# AUDIO_CODEC_CS4270-B.net
KiCad netlist of a schematic drawn in Altium Designer
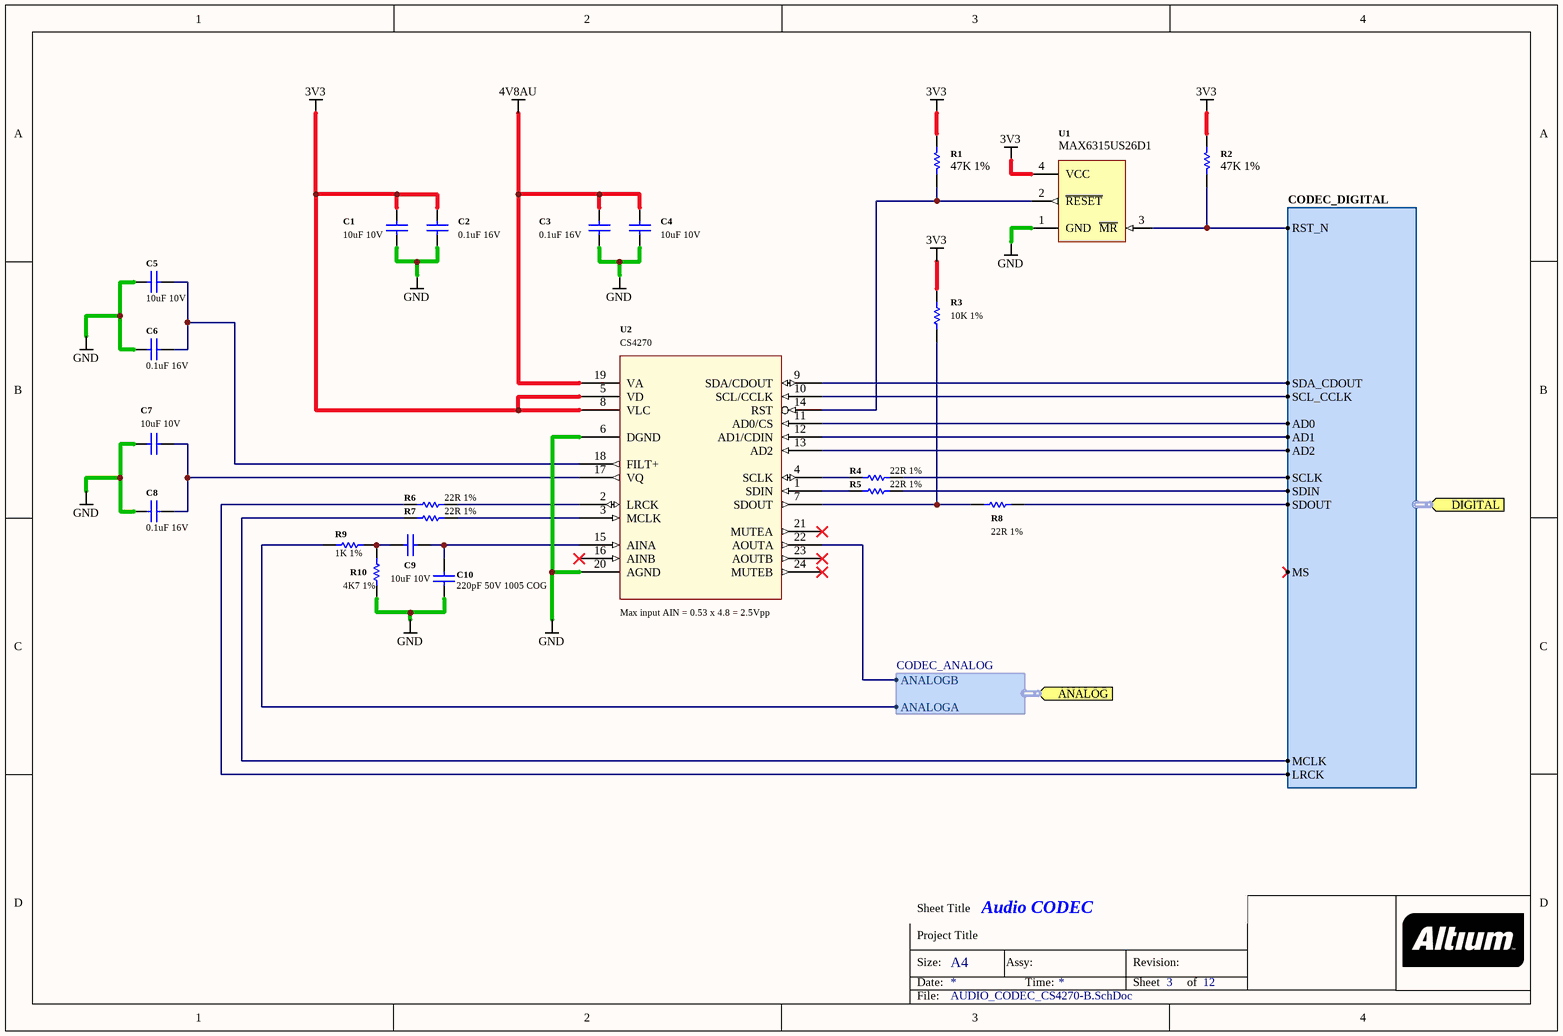
[diagram p0: AUDIO_CODEC_CS4270-B.SchDoc]

(export (version "E")
  (design (tool "Eeschema 10.0.6"))
  (components
    (comp (ref "C1")
      (value "10uF 10V")
      (footprint "CAPC2012-STAR")
      (description "Capacitor, Ceramic, 10uF 10% 10V 0805 (2012) X5R")
      (fields (field (name "TOLERANCE") "10 %"))
      (libsource (lib "AltiumDesignLibrary") (part "CAP-NP"))
    )
    (comp (ref "C2")
      (value "0.1uF 16V")
      (footprint "CAPC1005-STAR")
      (description "Capacitor, Ceramic, 0.1uF 10% 16V 0402 (1005) X7R")
      (fields (field (name "TOLERANCE") "10 %"))
      (libsource (lib "AltiumDesignLibrary") (part "CAP-NP"))
    )
    (comp (ref "C3")
      (value "0.1uF 16V")
      (footprint "CAPC1005-STAR")
      (description "Capacitor, Ceramic, 0.1uF 10% 16V 0402 (1005) X7R")
      (fields (field (name "TOLERANCE") "10 %"))
      (libsource (lib "AltiumDesignLibrary") (part "CAP-NP"))
    )
    (comp (ref "C4")
      (value "10uF 10V")
      (footprint "CAPC2012-STAR")
      (description "Capacitor, Ceramic, 10uF 10% 10V 0805 (2012) X5R")
      (fields (field (name "TOLERANCE") "10 %"))
      (libsource (lib "AltiumDesignLibrary") (part "CAP-NP"))
    )
    (comp (ref "C5")
      (value "10uF 10V")
      (footprint "CAPC2012-STAR")
      (description "Capacitor, Ceramic, 10uF 10% 10V 0805 (2012) X5R")
      (fields (field (name "TOLERANCE") "10 %"))
      (libsource (lib "AltiumDesignLibrary") (part "CAP-NP"))
    )
    (comp (ref "C6")
      (value "0.1uF 16V")
      (footprint "CAPC1005-STAR")
      (description "Capacitor, Ceramic, 0.1uF 10% 16V 0402 (1005) X7R")
      (fields (field (name "TOLERANCE") "10 %"))
      (libsource (lib "AltiumDesignLibrary") (part "CAP-NP"))
    )
    (comp (ref "C7")
      (value "10uF 10V")
      (footprint "CAPC2012-STAR")
      (description "Capacitor, Ceramic, 10uF 10% 10V 0805 (2012) X5R")
      (fields (field (name "TOLERANCE") "10 %"))
      (libsource (lib "AltiumDesignLibrary") (part "CAP-NP"))
    )
    (comp (ref "C8")
      (value "0.1uF 16V")
      (footprint "CAPC1005-STAR")
      (description "Capacitor, Ceramic, 0.1uF 10% 16V 0402 (1005) X7R")
      (fields (field (name "TOLERANCE") "10 %"))
      (libsource (lib "AltiumDesignLibrary") (part "CAP-NP"))
    )
    (comp (ref "C9")
      (value "10uF 10V")
      (footprint "CAPC2012-STAR")
      (description "Capacitor, Ceramic, 10uF 10% 10V 0805 (2012) X5R")
      (fields (field (name "TOLERANCE") "10 %"))
      (libsource (lib "AltiumDesignLibrary") (part "CAP-NP"))
    )
    (comp (ref "C10")
      (value "220pF 50V 1005 COG")
      (footprint "CAPC1005-STAR")
      (description "Capacitor, Ceramic, 220pF 5% 50V 0402 (1005) COG")
      (fields (field (name "TOLERANCE") "5 %"))
      (libsource (lib "AltiumDesignLibrary") (part "CAP-NP"))
    )
    (comp (ref "R1")
      (value "47K 1%")
      (footprint "RESC1005-STAR")
      (description "Resistor, 47K 1% 0402 (1005)")
      (fields (field (name "TOLERANCE") "1 %"))
      (libsource (lib "AltiumDesignLibrary") (part "RES"))
    )
    (comp (ref "R2")
      (value "47K 1%")
      (footprint "RESC1005-STAR")
      (description "Resistor, 47K 1% 0402 (1005)")
      (fields (field (name "TOLERANCE") "1 %"))
      (libsource (lib "AltiumDesignLibrary") (part "RES"))
    )
    (comp (ref "R3")
      (value "10K 1%")
      (footprint "RESC1005-STAR")
      (description "Resistor, 10K 1% 0402 (1005)")
      (fields (field (name "TOLERANCE") "1 %"))
      (libsource (lib "AltiumDesignLibrary") (part "RES"))
    )
    (comp (ref "R4")
      (value "22R 1%")
      (footprint "RESC1005-STAR")
      (description "Resistor, 22R 1% 0402 (1005)")
      (fields (field (name "TOLERANCE") "1 %"))
      (libsource (lib "AltiumDesignLibrary") (part "RES"))
    )
    (comp (ref "R5")
      (value "22R 1%")
      (footprint "RESC1005-STAR")
      (description "Resistor, 22R 1% 0402 (1005)")
      (fields (field (name "TOLERANCE") "1 %"))
      (libsource (lib "AltiumDesignLibrary") (part "RES"))
    )
    (comp (ref "R6")
      (value "22R 1%")
      (footprint "RESC1005-STAR")
      (description "Resistor, 22R 1% 0402 (1005)")
      (fields (field (name "TOLERANCE") "1 %"))
      (libsource (lib "AltiumDesignLibrary") (part "RES"))
    )
    (comp (ref "R7")
      (value "22R 1%")
      (footprint "RESC1005-STAR")
      (description "Resistor, 22R 1% 0402 (1005)")
      (fields (field (name "TOLERANCE") "1 %"))
      (libsource (lib "AltiumDesignLibrary") (part "RES"))
    )
    (comp (ref "R8")
      (value "22R 1%")
      (footprint "RESC1005-STAR")
      (description "Resistor, 22R 1% 0402 (1005)")
      (fields (field (name "TOLERANCE") "1 %"))
      (libsource (lib "AltiumDesignLibrary") (part "RES"))
    )
    (comp (ref "R9")
      (value "1K 1%")
      (footprint "RESC1005-STAR")
      (description "Resistor, 1K 1% 0402 (1005)")
      (fields (field (name "TOLERANCE") "1 %"))
      (libsource (lib "AltiumDesignLibrary") (part "RES"))
    )
    (comp (ref "R10")
      (value "4K7 1%")
      (footprint "RESC1005-STAR")
      (description "Resistor, 4K7 1% 0402 (1005)")
      (fields (field (name "TOLERANCE") "1 %"))
      (libsource (lib "AltiumDesignLibrary") (part "RES"))
    )
    (comp (ref "U1")
      (value "MAX6315US26D1")
      (footprint "SOT143")
      (description "MAX6315, Open-Drain Output SOT Reset IC, Customized Reset Thresholds, Timeout Delays")
      (libsource (lib "AltiumDesignLibrary") (part "MAX6315"))
    )
    (comp (ref "U2")
      (value "CS4270")
      (footprint "TSSOP-24")
      (description "CS4270; 24-Bit, 192 kHz Stereo Audio CODEC")
      (libsource (lib "AltiumDesignLibrary") (part "CS4270"))
    )
  )
  (nets
    (net (code "3") (name "/AD0") (class "Default")
      (node (ref "U2") (pin "11") (pinfunction "AD0/CS_11") (pintype "input"))
    )
    (net (code "4") (name "/AD1") (class "Default")
      (node (ref "U2") (pin "12") (pinfunction "AD1/CDIN_12") (pintype "input"))
    )
    (net (code "5") (name "/AD2") (class "Default")
      (node (ref "U2") (pin "13") (pinfunction "AD2_13") (pintype "input"))
    )
    (net (code "6") (name "/ANALOGA") (class "Default")
      (node (ref "R9") (pin "1") (pinfunction "1_1") (pintype "passive"))
    )
    (net (code "7") (name "/ANALOGB") (class "Default")
      (node (ref "U2") (pin "22") (pinfunction "AOUTA_22") (pintype "output"))
    )
    (net (code "8") (name "/LRCK") (class "Default")
      (node (ref "R6") (pin "1") (pinfunction "1_1") (pintype "passive"))
    )
    (net (code "9") (name "/MCLK") (class "Default")
      (node (ref "R7") (pin "1") (pinfunction "1_1") (pintype "passive"))
    )
    (net (code "10") (name "/RST_N") (class "Default")
      (node (ref "R2") (pin "1") (pinfunction "1_1") (pintype "passive"))
      (node (ref "U1") (pin "3") (pinfunction "~{MR}_3") (pintype "input"))
    )
    (net (code "11") (name "/SCLK") (class "Default")
      (node (ref "R4") (pin "2") (pinfunction "2_2") (pintype "passive"))
    )
    (net (code "12") (name "/SCL_CCLK") (class "Default")
      (node (ref "U2") (pin "10") (pinfunction "SCL/CCLK_10") (pintype "input"))
    )
    (net (code "13") (name "/SDA_CDOUT") (class "Default")
      (node (ref "U2") (pin "9") (pinfunction "SDA/CDOUT_9") (pintype "bidirectional"))
    )
    (net (code "14") (name "/SDIN") (class "Default")
      (node (ref "R5") (pin "2") (pinfunction "2_2") (pintype "passive"))
    )
    (net (code "15") (name "/SDOUT") (class "Default")
      (node (ref "R8") (pin "2") (pinfunction "2_2") (pintype "passive"))
    )
    (net (code "18") (name "3V3") (class "Default")
      (node (ref "C1") (pin "1") (pinfunction "1_1") (pintype "passive"))
      (node (ref "C2") (pin "1") (pinfunction "1_1") (pintype "passive"))
      (node (ref "R1") (pin "2") (pinfunction "2_2") (pintype "passive"))
      (node (ref "R2") (pin "2") (pinfunction "2_2") (pintype "passive"))
      (node (ref "R3") (pin "1") (pinfunction "1_1") (pintype "passive"))
      (node (ref "U1") (pin "4") (pinfunction "VCC_4") (pintype "power_in"))
      (node (ref "U2") (pin "5") (pinfunction "VD_5") (pintype "power_in"))
      (node (ref "U2") (pin "8") (pinfunction "VLC_8") (pintype "power_in"))
    )
    (net (code "19") (name "4V8AU") (class "Default")
      (node (ref "C3") (pin "1") (pinfunction "1_1") (pintype "passive"))
      (node (ref "C4") (pin "1") (pinfunction "1_1") (pintype "passive"))
      (node (ref "U2") (pin "19") (pinfunction "VA_19") (pintype "power_in"))
    )
    (net (code "20") (name "GND") (class "Default")
      (node (ref "C1") (pin "2") (pinfunction "2_2") (pintype "passive"))
      (node (ref "C10") (pin "2") (pinfunction "2_2") (pintype "passive"))
      (node (ref "C2") (pin "2") (pinfunction "2_2") (pintype "passive"))
      (node (ref "C3") (pin "2") (pinfunction "2_2") (pintype "passive"))
      (node (ref "C4") (pin "2") (pinfunction "2_2") (pintype "passive"))
      (node (ref "C5") (pin "2") (pinfunction "2_2") (pintype "passive"))
      (node (ref "C6") (pin "1") (pinfunction "1_1") (pintype "passive"))
      (node (ref "C7") (pin "2") (pinfunction "2_2") (pintype "passive"))
      (node (ref "C8") (pin "2") (pinfunction "2_2") (pintype "passive"))
      (node (ref "R10") (pin "1") (pinfunction "1_1") (pintype "passive"))
      (node (ref "U1") (pin "1") (pinfunction "GND_1") (pintype "power_in"))
      (node (ref "U2") (pin "20") (pinfunction "AGND_20") (pintype "power_in"))
      (node (ref "U2") (pin "6") (pinfunction "DGND_6") (pintype "power_in"))
    )
    (net (code "21") (name "Net-(C9-Pad2)") (class "Default")
      (node (ref "C9") (pin "2") (pinfunction "2_2") (pintype "passive"))
      (node (ref "R10") (pin "2") (pinfunction "2_2") (pintype "passive"))
      (node (ref "R9") (pin "2") (pinfunction "2_2") (pintype "passive"))
    )
    (net (code "22") (name "Net-(U1-~{RESET})") (class "Default")
      (node (ref "R1") (pin "1") (pinfunction "1_1") (pintype "passive"))
      (node (ref "U1") (pin "2") (pinfunction "~{RESET}_2") (pintype "output"))
      (node (ref "U2") (pin "14") (pinfunction "RST_14") (pintype "input"))
    )
    (net (code "23") (name "Net-(U2-AINA)") (class "Default")
      (node (ref "C10") (pin "1") (pinfunction "1_1") (pintype "passive"))
      (node (ref "C9") (pin "1") (pinfunction "1_1") (pintype "passive"))
      (node (ref "U2") (pin "15") (pinfunction "AINA_15") (pintype "input"))
    )
    (net (code "24") (name "Net-(U2-FILT+)") (class "Default")
      (node (ref "C5") (pin "1") (pinfunction "1_1") (pintype "passive"))
      (node (ref "C6") (pin "2") (pinfunction "2_2") (pintype "passive"))
      (node (ref "U2") (pin "18") (pinfunction "FILT+_18") (pintype "output"))
    )
    (net (code "25") (name "Net-(U2-LRCK)") (class "Default")
      (node (ref "R6") (pin "2") (pinfunction "2_2") (pintype "passive"))
      (node (ref "U2") (pin "2") (pinfunction "LRCK_2") (pintype "bidirectional"))
    )
    (net (code "26") (name "Net-(U2-MCLK)") (class "Default")
      (node (ref "R7") (pin "2") (pinfunction "2_2") (pintype "passive"))
      (node (ref "U2") (pin "3") (pinfunction "MCLK_3") (pintype "input"))
    )
    (net (code "27") (name "Net-(U2-SCLK)") (class "Default")
      (node (ref "R4") (pin "1") (pinfunction "1_1") (pintype "passive"))
      (node (ref "U2") (pin "4") (pinfunction "SCLK_4") (pintype "bidirectional"))
    )
    (net (code "28") (name "Net-(U2-SDIN)") (class "Default")
      (node (ref "R5") (pin "1") (pinfunction "1_1") (pintype "passive"))
      (node (ref "U2") (pin "1") (pinfunction "SDIN_1") (pintype "input"))
    )
    (net (code "29") (name "Net-(U2-SDOUT)") (class "Default")
      (node (ref "R3") (pin "2") (pinfunction "2_2") (pintype "passive"))
      (node (ref "R8") (pin "1") (pinfunction "1_1") (pintype "passive"))
      (node (ref "U2") (pin "7") (pinfunction "SDOUT_7") (pintype "output"))
    )
    (net (code "30") (name "Net-(U2-VQ)") (class "Default")
      (node (ref "C7") (pin "1") (pinfunction "1_1") (pintype "passive"))
      (node (ref "C8") (pin "1") (pinfunction "1_1") (pintype "passive"))
      (node (ref "U2") (pin "17") (pinfunction "VQ_17") (pintype "output"))
    )
    (net (code "31") (name "unconnected-(U2-AINB-Pad16)") (class "Default")
      (node (ref "U2") (pin "16") (pinfunction "AINB_16") (pintype "input+no_connect"))
    )
    (net (code "32") (name "unconnected-(U2-AOUTB-Pad23)") (class "Default")
      (node (ref "U2") (pin "23") (pinfunction "AOUTB_23") (pintype "output+no_connect"))
    )
    (net (code "33") (name "unconnected-(U2-MUTEA-Pad21)") (class "Default")
      (node (ref "U2") (pin "21") (pinfunction "MUTEA_21") (pintype "output+no_connect"))
    )
    (net (code "34") (name "unconnected-(U2-MUTEB-Pad24)") (class "Default")
      (node (ref "U2") (pin "24") (pinfunction "MUTEB_24") (pintype "output+no_connect"))
    )
  )
)
